# USBHost.net
KiCad netlist of a schematic drawn in Altium Designer
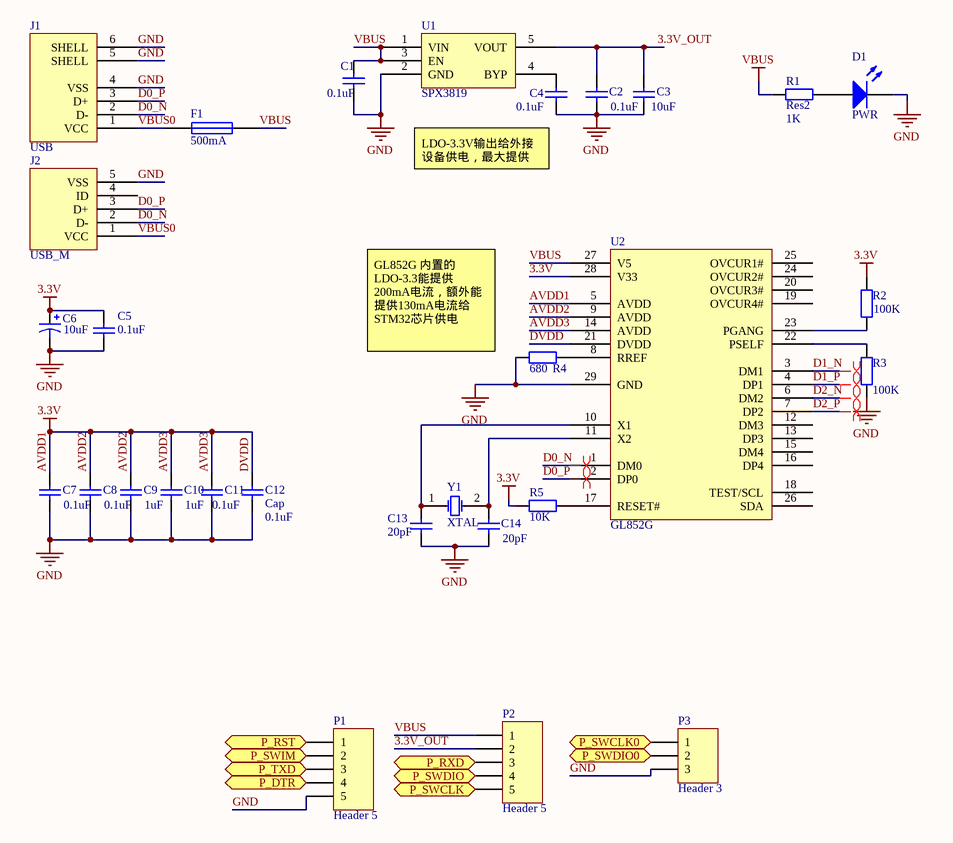
[diagram p0: USBHost.SchDoc]

(export (version "E")
  (design (tool "Eeschema 10.0.6"))
  (components
    (comp (ref "C1")
      (value "0.1uF")
      (footprint "C-0603")
      (description "Capacitor")
      (fields (field (name "Comment") "Cap") (field (name "PUBLISHER") "Altium Limited"))
      (libsource (lib "Miscellaneous Devices") (part "Cap"))
    )
    (comp (ref "C2")
      (value "0.1uF")
      (footprint "C-0603")
      (description "Capacitor")
      (fields (field (name "Comment") "Cap") (field (name "PUBLISHER") "Altium Limited"))
      (libsource (lib "Miscellaneous Devices") (part "Cap"))
    )
    (comp (ref "C3")
      (value "10uF")
      (footprint "C-0603")
      (description "Capacitor")
      (fields (field (name "Comment") "Cap") (field (name "PUBLISHER") "Altium Limited"))
      (libsource (lib "Miscellaneous Devices") (part "Cap"))
    )
    (comp (ref "C4")
      (value "0.1uF")
      (footprint "C-0603")
      (description "Capacitor")
      (fields (field (name "Comment") "Cap") (field (name "PUBLISHER") "Altium Limited"))
      (libsource (lib "Miscellaneous Devices") (part "Cap"))
    )
    (comp (ref "C5")
      (value "0.1uF")
      (footprint "C-0603")
      (description "Capacitor")
      (fields (field (name "Comment") "Cap") (field (name "PUBLISHER") "Altium Limited"))
      (libsource (lib "Miscellaneous Devices") (part "Cap"))
    )
    (comp (ref "C6")
      (value "10uF")
      (footprint "C-0603")
      (description "Polarized Capacitor (Radial)")
      (fields (field (name "Comment") "Cap Pol1") (field (name "PUBLISHER") "Altium Limited"))
      (libsource (lib "Miscellaneous Devices") (part "Cap Pol1"))
    )
    (comp (ref "C7")
      (value "0.1uF")
      (footprint "C-0603")
      (description "Capacitor")
      (fields (field (name "Comment") "Cap") (field (name "PUBLISHER") "Altium Limited"))
      (libsource (lib "Miscellaneous Devices") (part "Cap"))
    )
    (comp (ref "C8")
      (value "0.1uF")
      (footprint "C-0603")
      (description "Capacitor")
      (fields (field (name "Comment") "Cap") (field (name "PUBLISHER") "Altium Limited"))
      (libsource (lib "Miscellaneous Devices") (part "Cap"))
    )
    (comp (ref "C9")
      (value "1uF")
      (footprint "C-0603")
      (description "Capacitor")
      (fields (field (name "Comment") "Cap") (field (name "PUBLISHER") "Altium Limited"))
      (libsource (lib "Miscellaneous Devices") (part "Cap"))
    )
    (comp (ref "C10")
      (value "1uF")
      (footprint "C-0603")
      (description "Capacitor")
      (fields (field (name "Comment") "Cap") (field (name "PUBLISHER") "Altium Limited"))
      (libsource (lib "Miscellaneous Devices") (part "Cap"))
    )
    (comp (ref "C11")
      (value "0.1uF")
      (footprint "C-0603")
      (description "Capacitor")
      (fields (field (name "Comment") "Cap") (field (name "PUBLISHER") "Altium Limited"))
      (libsource (lib "Miscellaneous Devices") (part "Cap"))
    )
    (comp (ref "C12")
      (value "Cap")
      (footprint "C-0603")
      (description "Capacitor")
      (fields (field (name "ALTIUM_VALUE") "0.1uF") (field (name "PUBLISHER") "Altium Limited"))
      (libsource (lib "Miscellaneous Devices") (part "Cap"))
    )
    (comp (ref "C13")
      (value "20pF")
      (footprint "C-0603")
      (description "Capacitor")
      (fields (field (name "Comment") "Cap") (field (name "PUBLISHER") "Altium Limited"))
      (libsource (lib "Miscellaneous Devices") (part "Cap"))
    )
    (comp (ref "C14")
      (value "20pF")
      (footprint "C-0603")
      (description "Capacitor")
      (fields (field (name "Comment") "Cap") (field (name "PUBLISHER") "Altium Limited"))
      (libsource (lib "Miscellaneous Devices") (part "Cap"))
    )
    (comp (ref "D1")
      (value "PWR")
      (footprint "SMT_LED_0603")
      (description "Typical RED, GREEN, YELLOW, AMBER GaAs LED")
      (fields (field (name "PUBLISHER") "Altium Limited"))
      (libsource (lib "Miscellaneous Devices") (part "LED2"))
    )
    (comp (ref "F1")
      (value "500mA")
      (footprint "0805-1")
      (description "保险丝")
      (fields (field (name "Comment") "Fuse1"))
      (libsource (lib "Fszhang") (part "Fuse1"))
    )
    (comp (ref "J1")
      (value "USB")
      (footprint "USB-B")
      (description "USB接口")
      (libsource (lib "HDR_Fszhang") (part "USB"))
    )
    (comp (ref "J2")
      (value "USB_M")
      (footprint "USB_MICRO_5S_B")
      (description "Micro/Mini USB")
      (libsource (lib "HDR_Fszhang") (part "USB_M"))
    )
    (comp (ref "P1")
      (value "Header 5")
      (footprint "HEADER 5")
      (description "Header, 5-Pin")
      (fields (field (name "PUBLISHER") "Altium Limited"))
      (libsource (lib "Miscellaneous Connectors") (part "Header 5"))
    )
    (comp (ref "P2")
      (value "Header 5")
      (footprint "HEADER 5")
      (description "Header, 5-Pin")
      (fields (field (name "PUBLISHER") "Altium Limited"))
      (libsource (lib "Miscellaneous Connectors") (part "Header 5"))
    )
    (comp (ref "P3")
      (value "Header 3")
      (footprint "SIP3-1.27")
      (description "Header, 3-Pin")
      (fields (field (name "PUBLISHER") "Altium Limited"))
      (libsource (lib "Miscellaneous Connectors") (part "Header 3"))
    )
    (comp (ref "R1")
      (value "Res2")
      (footprint "0603-1")
      (description "Resistor")
      (fields (field (name "ALTIUM_VALUE") "1K") (field (name "PUBLISHER") "Altium Limited"))
      (libsource (lib "") (part "Res2_1"))
    )
    (comp (ref "R2")
      (value "100K")
      (footprint "0603-1")
      (description "Resistor")
      (fields (field (name "Comment") "Res2") (field (name "PUBLISHER") "Altium Limited"))
      (libsource (lib "") (part "Res2_2"))
    )
    (comp (ref "R3")
      (value "100K")
      (footprint "0603-1")
      (description "Resistor")
      (fields (field (name "Comment") "Res2") (field (name "PUBLISHER") "Altium Limited"))
      (libsource (lib "") (part "Res2_2"))
    )
    (comp (ref "R4")
      (value "680")
      (footprint "0603-1")
      (description "贴片电阻")
      (fields (field (name "Comment") "Res1") (field (name "PUBLISHER") "Altium Limited"))
      (libsource (lib "Fszhang") (part "Res1"))
    )
    (comp (ref "R5")
      (value "10K")
      (footprint "0603-1")
      (description "Resistor")
      (fields (field (name "Comment") "Res2") (field (name "PUBLISHER") "Altium Limited"))
      (libsource (lib "Miscellaneous Devices") (part "Res2"))
    )
    (comp (ref "U1") (value "SPX3819") (footprint "SOT23-5") (libsource (lib "Schlib1") (part "SPX3819")))
    (comp (ref "U2") (value "GL852G") (footprint "QFN28-L") (libsource (lib "Schlib1") (part "GL852G")))
    (comp (ref "Y1")
      (value "XTAL")
      (footprint "XAL5032 2-Leads")
      (description "Crystal Oscillator")
      (fields (field (name "PUBLISHER") "Altium Limited"))
      (libsource (lib "Miscellaneous Devices") (part "XTAL"))
    )
  )
  (nets
    (net (code "1") (name "/3.3V_OUT") (class "Default")
      (node (ref "C2") (pin "2") (pinfunction "2_2") (pintype "passive"))
      (node (ref "C3") (pin "2") (pinfunction "2_2") (pintype "passive"))
      (node (ref "P2") (pin "2") (pinfunction "2_2") (pintype "passive"))
      (node (ref "U1") (pin "5") (pinfunction "VOUT_5") (pintype "passive"))
    )
    (net (code "2") (name "/D0_N") (class "Default")
      (node (ref "J1") (pin "2") (pinfunction "D-_2") (pintype "passive"))
      (node (ref "J2") (pin "2") (pinfunction "D-_2") (pintype "passive"))
      (node (ref "U2") (pin "1") (pinfunction "DM0_1") (pintype "passive"))
    )
    (net (code "3") (name "/D0_P") (class "Default")
      (node (ref "J1") (pin "3") (pinfunction "D+_3") (pintype "passive"))
      (node (ref "J2") (pin "3") (pinfunction "D+_3") (pintype "passive"))
      (node (ref "U2") (pin "2") (pinfunction "DP0_2") (pintype "passive"))
    )
    (net (code "4") (name "/D1_N") (class "Default")
      (node (ref "U2") (pin "3") (pinfunction "DM1_3") (pintype "passive"))
    )
    (net (code "5") (name "/D1_P") (class "Default")
      (node (ref "U2") (pin "4") (pinfunction "DP1_4") (pintype "passive"))
    )
    (net (code "6") (name "/D2_N") (class "Default")
      (node (ref "U2") (pin "6") (pinfunction "DM2_6") (pintype "passive"))
    )
    (net (code "7") (name "/D2_P") (class "Default")
      (node (ref "U2") (pin "7") (pinfunction "DP2_7") (pintype "passive"))
    )
    (net (code "8") (name "/P_DTR") (class "Default")
      (node (ref "P1") (pin "4") (pinfunction "4_4") (pintype "passive"))
    )
    (net (code "9") (name "/P_RST") (class "Default")
      (node (ref "P1") (pin "1") (pinfunction "1_1") (pintype "passive"))
    )
    (net (code "10") (name "/P_RXD") (class "Default")
      (node (ref "P2") (pin "3") (pinfunction "3_3") (pintype "passive"))
    )
    (net (code "11") (name "/P_SWCLK") (class "Default")
      (node (ref "P2") (pin "5") (pinfunction "5_5") (pintype "passive"))
    )
    (net (code "12") (name "/P_SWCLK0") (class "Default")
      (node (ref "P3") (pin "1") (pinfunction "1_1") (pintype "passive"))
    )
    (net (code "13") (name "/P_SWDIO") (class "Default")
      (node (ref "P2") (pin "4") (pinfunction "4_4") (pintype "passive"))
    )
    (net (code "14") (name "/P_SWDIO0") (class "Default")
      (node (ref "P3") (pin "2") (pinfunction "2_2") (pintype "passive"))
    )
    (net (code "15") (name "/P_SWIM") (class "Default")
      (node (ref "P1") (pin "2") (pinfunction "2_2") (pintype "passive"))
    )
    (net (code "16") (name "/P_TXD") (class "Default")
      (node (ref "P1") (pin "3") (pinfunction "3_3") (pintype "passive"))
    )
    (net (code "17") (name "/VBUS0") (class "Default")
      (node (ref "F1") (pin "2") (pinfunction "2_2") (pintype "passive"))
      (node (ref "J1") (pin "1") (pinfunction "VCC_1") (pintype "passive"))
      (node (ref "J2") (pin "1") (pinfunction "VCC_1") (pintype "passive"))
    )
    (net (code "18") (name "3.3V") (class "Default")
      (node (ref "C10") (pin "2") (pinfunction "2_2") (pintype "passive"))
      (node (ref "C11") (pin "2") (pinfunction "2_2") (pintype "passive"))
      (node (ref "C12") (pin "2") (pinfunction "2_2") (pintype "passive"))
      (node (ref "C5") (pin "1") (pinfunction "1_1") (pintype "passive"))
      (node (ref "C6") (pin "1") (pinfunction "1_1") (pintype "passive"))
      (node (ref "C7") (pin "2") (pinfunction "2_2") (pintype "passive"))
      (node (ref "C8") (pin "2") (pinfunction "2_2") (pintype "passive"))
      (node (ref "C9") (pin "2") (pinfunction "2_2") (pintype "passive"))
      (node (ref "R2") (pin "2") (pinfunction "2_2") (pintype "passive"))
      (node (ref "R5") (pin "2") (pinfunction "2_2") (pintype "passive"))
      (node (ref "U2") (pin "14") (pinfunction "AVDD_14") (pintype "passive"))
      (node (ref "U2") (pin "21") (pinfunction "DVDD_21") (pintype "passive"))
      (node (ref "U2") (pin "28") (pinfunction "V33_28") (pintype "passive"))
      (node (ref "U2") (pin "5") (pinfunction "AVDD_5") (pintype "passive"))
      (node (ref "U2") (pin "9") (pinfunction "AVDD_9") (pintype "passive"))
    )
    (net (code "19") (name "GND") (class "Default")
      (node (ref "C1") (pin "1") (pinfunction "1_1") (pintype "passive"))
      (node (ref "C10") (pin "1") (pinfunction "1_1") (pintype "passive"))
      (node (ref "C11") (pin "1") (pinfunction "1_1") (pintype "passive"))
      (node (ref "C12") (pin "1") (pinfunction "1_1") (pintype "passive"))
      (node (ref "C13") (pin "1") (pinfunction "1_1") (pintype "passive"))
      (node (ref "C14") (pin "1") (pinfunction "1_1") (pintype "passive"))
      (node (ref "C2") (pin "1") (pinfunction "1_1") (pintype "passive"))
      (node (ref "C3") (pin "1") (pinfunction "1_1") (pintype "passive"))
      (node (ref "C4") (pin "1") (pinfunction "1_1") (pintype "passive"))
      (node (ref "C5") (pin "2") (pinfunction "2_2") (pintype "passive"))
      (node (ref "C6") (pin "2") (pinfunction "2_2") (pintype "passive"))
      (node (ref "C7") (pin "1") (pinfunction "1_1") (pintype "passive"))
      (node (ref "C8") (pin "1") (pinfunction "1_1") (pintype "passive"))
      (node (ref "C9") (pin "1") (pinfunction "1_1") (pintype "passive"))
      (node (ref "D1") (pin "2") (pinfunction "K_2") (pintype "passive"))
      (node (ref "J1") (pin "4") (pinfunction "VSS_4") (pintype "passive"))
      (node (ref "J1") (pin "5") (pinfunction "SHELL_5") (pintype "passive"))
      (node (ref "J1") (pin "6") (pinfunction "SHELL_6") (pintype "passive"))
      (node (ref "J2") (pin "5") (pinfunction "VSS_5") (pintype "passive"))
      (node (ref "P1") (pin "5") (pinfunction "5_5") (pintype "passive"))
      (node (ref "P3") (pin "3") (pinfunction "3_3") (pintype "passive"))
      (node (ref "R3") (pin "1") (pinfunction "1_1") (pintype "passive"))
      (node (ref "R4") (pin "1") (pinfunction "1_1") (pintype "passive"))
      (node (ref "U1") (pin "2") (pinfunction "GND_2") (pintype "passive"))
      (node (ref "U2") (pin "29") (pinfunction "GND_29") (pintype "passive"))
    )
    (net (code "20") (name "Net-(D1-A)") (class "Default")
      (node (ref "D1") (pin "1") (pinfunction "A_1") (pintype "passive"))
      (node (ref "R1") (pin "2") (pinfunction "2_2") (pintype "passive"))
    )
    (net (code "21") (name "Net-(U1-BYP)") (class "Default")
      (node (ref "C4") (pin "2") (pinfunction "2_2") (pintype "passive"))
      (node (ref "U1") (pin "4") (pinfunction "BYP_4") (pintype "passive"))
    )
    (net (code "22") (name "Net-(U2-PGANG)") (class "Default")
      (node (ref "R2") (pin "1") (pinfunction "1_1") (pintype "passive"))
      (node (ref "U2") (pin "23") (pinfunction "PGANG_23") (pintype "passive"))
    )
    (net (code "23") (name "Net-(U2-PSELF)") (class "Default")
      (node (ref "R3") (pin "2") (pinfunction "2_2") (pintype "passive"))
      (node (ref "U2") (pin "22") (pinfunction "PSELF_22") (pintype "passive"))
    )
    (net (code "24") (name "Net-(U2-RESET#)") (class "Default")
      (node (ref "R5") (pin "1") (pinfunction "1_1") (pintype "passive"))
      (node (ref "U2") (pin "17") (pinfunction "RESET#_17") (pintype "passive"))
    )
    (net (code "25") (name "Net-(U2-RREF)") (class "Default")
      (node (ref "R4") (pin "2") (pinfunction "2_2") (pintype "passive"))
      (node (ref "U2") (pin "8") (pinfunction "RREF_8") (pintype "passive"))
    )
    (net (code "26") (name "Net-(U2-X1)") (class "Default")
      (node (ref "C13") (pin "2") (pinfunction "2_2") (pintype "passive"))
      (node (ref "U2") (pin "10") (pinfunction "X1_10") (pintype "passive"))
      (node (ref "Y1") (pin "1") (pinfunction "OSC1_1") (pintype "passive"))
    )
    (net (code "27") (name "Net-(U2-X2)") (class "Default")
      (node (ref "C14") (pin "2") (pinfunction "2_2") (pintype "passive"))
      (node (ref "U2") (pin "11") (pinfunction "X2_11") (pintype "passive"))
      (node (ref "Y1") (pin "2") (pinfunction "OSC2_2") (pintype "passive"))
    )
    (net (code "28") (name "VBUS") (class "Default")
      (node (ref "C1") (pin "2") (pinfunction "2_2") (pintype "passive"))
      (node (ref "F1") (pin "1") (pinfunction "1_1") (pintype "passive"))
      (node (ref "P2") (pin "1") (pinfunction "1_1") (pintype "passive"))
      (node (ref "R1") (pin "1") (pinfunction "1_1") (pintype "passive"))
      (node (ref "U1") (pin "1") (pinfunction "VIN_1") (pintype "passive"))
      (node (ref "U1") (pin "3") (pinfunction "EN_3") (pintype "passive"))
      (node (ref "U2") (pin "27") (pinfunction "V5_27") (pintype "passive"))
    )
    (net (code "29") (name "unconnected-(J2-ID-Pad4)") (class "Default")
      (node (ref "J2") (pin "4") (pinfunction "ID_4") (pintype "passive"))
    )
    (net (code "30") (name "unconnected-(U2-DM3-Pad12)") (class "Default")
      (node (ref "U2") (pin "12") (pinfunction "DM3_12") (pintype "passive"))
    )
    (net (code "31") (name "unconnected-(U2-DM4-Pad15)") (class "Default")
      (node (ref "U2") (pin "15") (pinfunction "DM4_15") (pintype "passive"))
    )
    (net (code "32") (name "unconnected-(U2-DP3-Pad13)") (class "Default")
      (node (ref "U2") (pin "13") (pinfunction "DP3_13") (pintype "passive"))
    )
    (net (code "33") (name "unconnected-(U2-DP4-Pad16)") (class "Default")
      (node (ref "U2") (pin "16") (pinfunction "DP4_16") (pintype "passive"))
    )
    (net (code "34") (name "unconnected-(U2-OVCUR1#-Pad25)") (class "Default")
      (node (ref "U2") (pin "25") (pinfunction "OVCUR1#_25") (pintype "passive"))
    )
    (net (code "35") (name "unconnected-(U2-OVCUR2#-Pad24)") (class "Default")
      (node (ref "U2") (pin "24") (pinfunction "OVCUR2#_24") (pintype "passive"))
    )
    (net (code "36") (name "unconnected-(U2-OVCUR3#-Pad20)") (class "Default")
      (node (ref "U2") (pin "20") (pinfunction "OVCUR3#_20") (pintype "passive"))
    )
    (net (code "37") (name "unconnected-(U2-OVCUR4#-Pad19)") (class "Default")
      (node (ref "U2") (pin "19") (pinfunction "OVCUR4#_19") (pintype "passive"))
    )
    (net (code "38") (name "unconnected-(U2-SDA-Pad26)") (class "Default")
      (node (ref "U2") (pin "26") (pinfunction "SDA_26") (pintype "passive"))
    )
    (net (code "39") (name "unconnected-(U2-TEST{slash}SCL-Pad18)") (class "Default")
      (node (ref "U2") (pin "18") (pinfunction "TEST/SCL_18") (pintype "passive"))
    )
  )
)
